# schematic.net
KiCad netlist of a schematic drawn in EasyEDA
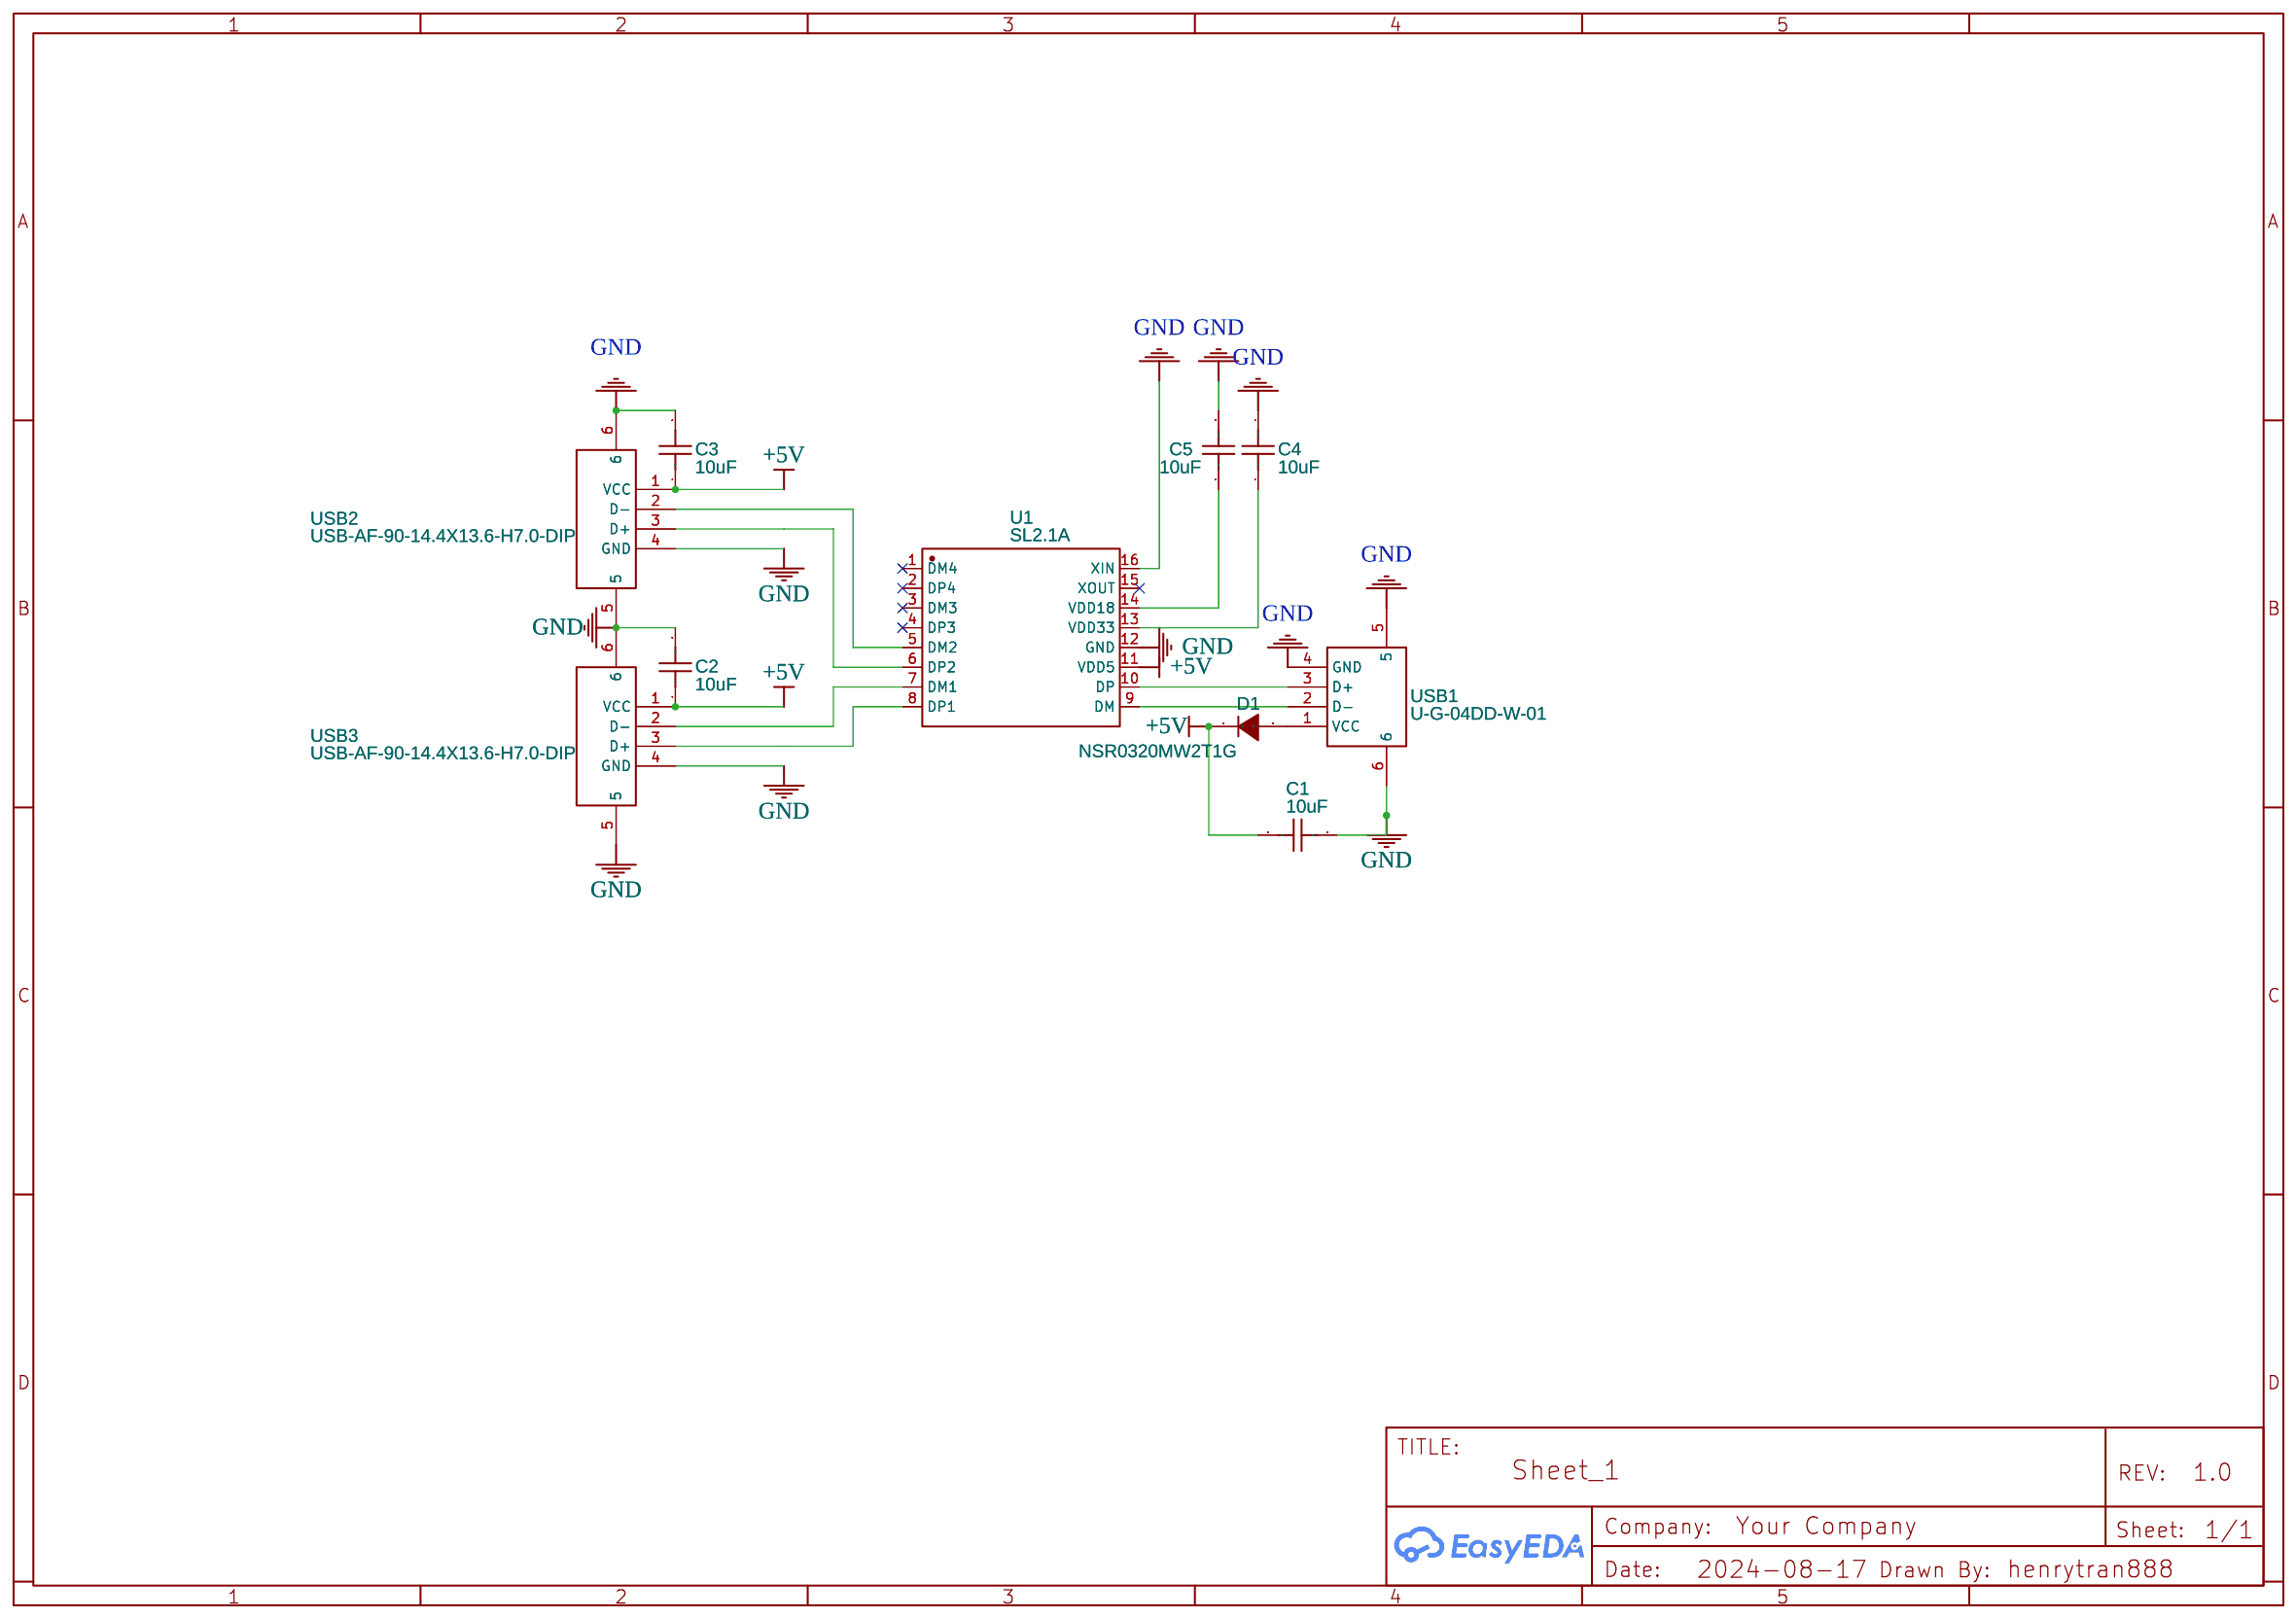
[diagram p0: schematic sheet]

(export (version "E")
  (design (tool "Eeschema 10.0.6"))
  (components
    (comp (ref "C1")
      (value "10uF")
      (fields
        (field (name "Manufacturer Part") "CL10A106KP8NNNC")
        (field (name "Manufacturer") "SAMSUNG(三星)")
      )
      (libsource (lib "") (part "CL10A106KP8NNNC_1"))
    )
    (comp (ref "C2")
      (value "10uF")
      (fields
        (field (name "Manufacturer Part") "CL10A106KP8NNNC")
        (field (name "Manufacturer") "SAMSUNG(三星)")
      )
      (libsource (lib "") (part "CL10A106KP8NNNC"))
    )
    (comp (ref "C3")
      (value "10uF")
      (fields
        (field (name "Manufacturer Part") "CL10A106KP8NNNC")
        (field (name "Manufacturer") "SAMSUNG(三星)")
      )
      (libsource (lib "") (part "CL10A106KP8NNNC"))
    )
    (comp (ref "C4")
      (value "10uF")
      (fields
        (field (name "Manufacturer Part") "CL10A106KP8NNNC")
        (field (name "Manufacturer") "SAMSUNG(三星)")
      )
      (libsource (lib "") (part "CL10A106KP8NNNC"))
    )
    (comp (ref "C5")
      (value "10uF")
      (fields
        (field (name "Manufacturer Part") "CL10A106KP8NNNC")
        (field (name "Manufacturer") "SAMSUNG(三星)")
      )
      (libsource (lib "") (part "CL10A106KP8NNNC"))
    )
    (comp (ref "D1")
      (value "NSR0320MW2T1G")
      (fields (field (name "Manufacturer") "onsemi(安森美)"))
      (libsource (lib "") (part "NSR0320MW2T1G"))
    )
    (comp (ref "U1")
      (value "SL2.1A")
      (fields (field (name "Manufacturer") "CoreChips(和芯润德)"))
      (libsource (lib "") (part "SL2.1A"))
    )
    (comp (ref "USB1")
      (value "U-G-04DD-W-01")
      (fields (field (name "Manufacturer Part") "U-G-O4DD-W-1") (field (name "Manufacturer") "韩国韩荣"))
      (libsource (lib "") (part "U-G-04DD-W-01"))
    )
    (comp (ref "USB2")
      (value "USB-AF-90-14.4X13.6-H7.0-DIP")
      (fields (field (name "Manufacturer Part") "903-131A1011D10100") (field (name "Manufacturer") "精拓金"))
      (libsource (lib "") (part "USB-AF-90-14.4X13.6-H7.0-DIP"))
    )
    (comp (ref "USB3")
      (value "USB-AF-90-14.4X13.6-H7.0-DIP")
      (fields (field (name "Manufacturer Part") "903-131A1011D10100") (field (name "Manufacturer") "精拓金"))
      (libsource (lib "") (part "USB-AF-90-14.4X13.6-H7.0-DIP"))
    )
  )
  (nets
    (net (code "1") (name "+5V") (class "Default")
      (node (ref "C1") (pin "1") (pinfunction "1_1") (pintype "unspecified"))
      (node (ref "C2") (pin "1") (pinfunction "1_1") (pintype "unspecified"))
      (node (ref "C3") (pin "1") (pinfunction "1_1") (pintype "unspecified"))
      (node (ref "D1") (pin "1") (pinfunction "C_1") (pintype "unspecified"))
      (node (ref "U1") (pin "11") (pinfunction "VDD5_11") (pintype "unspecified"))
      (node (ref "USB2") (pin "1") (pinfunction "VCC_1") (pintype "unspecified"))
      (node (ref "USB3") (pin "1") (pinfunction "VCC_1") (pintype "unspecified"))
    )
    (net (code "2") (name "GND") (class "Default")
      (node (ref "C1") (pin "2") (pinfunction "2_2") (pintype "unspecified"))
      (node (ref "C2") (pin "2") (pinfunction "2_2") (pintype "unspecified"))
      (node (ref "C3") (pin "2") (pinfunction "2_2") (pintype "unspecified"))
      (node (ref "C4") (pin "2") (pinfunction "2_2") (pintype "unspecified"))
      (node (ref "C5") (pin "2") (pinfunction "2_2") (pintype "unspecified"))
      (node (ref "U1") (pin "12") (pinfunction "GND_12") (pintype "unspecified"))
      (node (ref "U1") (pin "16") (pinfunction "XIN_16") (pintype "unspecified"))
      (node (ref "USB1") (pin "4") (pinfunction "GND_4") (pintype "unspecified"))
      (node (ref "USB1") (pin "5") (pinfunction "5_5") (pintype "unspecified"))
      (node (ref "USB1") (pin "6") (pinfunction "6_6") (pintype "unspecified"))
      (node (ref "USB2") (pin "4") (pinfunction "GND_4") (pintype "unspecified"))
      (node (ref "USB2") (pin "5") (pinfunction "5_5") (pintype "unspecified"))
      (node (ref "USB2") (pin "6") (pinfunction "6_6") (pintype "unspecified"))
      (node (ref "USB3") (pin "4") (pinfunction "GND_4") (pintype "unspecified"))
      (node (ref "USB3") (pin "5") (pinfunction "5_5") (pintype "unspecified"))
      (node (ref "USB3") (pin "6") (pinfunction "6_6") (pintype "unspecified"))
    )
    (net (code "3") (name "Net-(D1-A)") (class "Default")
      (node (ref "D1") (pin "2") (pinfunction "A_2") (pintype "unspecified"))
      (node (ref "USB1") (pin "1") (pinfunction "VCC_1") (pintype "unspecified"))
    )
    (net (code "4") (name "Net-(U1-DM)") (class "Default")
      (node (ref "U1") (pin "9") (pinfunction "DM_9") (pintype "unspecified"))
      (node (ref "USB1") (pin "2") (pinfunction "D-_2") (pintype "unspecified"))
    )
    (net (code "5") (name "Net-(U1-DM1)") (class "Default")
      (node (ref "U1") (pin "7") (pinfunction "DM1_7") (pintype "unspecified"))
      (node (ref "USB3") (pin "2") (pinfunction "D-_2") (pintype "unspecified"))
    )
    (net (code "6") (name "Net-(U1-DM2)") (class "Default")
      (node (ref "U1") (pin "5") (pinfunction "DM2_5") (pintype "unspecified"))
      (node (ref "USB2") (pin "2") (pinfunction "D-_2") (pintype "unspecified"))
    )
    (net (code "7") (name "Net-(U1-DP)") (class "Default")
      (node (ref "U1") (pin "10") (pinfunction "DP_10") (pintype "unspecified"))
      (node (ref "USB1") (pin "3") (pinfunction "D+_3") (pintype "unspecified"))
    )
    (net (code "8") (name "Net-(U1-DP1)") (class "Default")
      (node (ref "U1") (pin "8") (pinfunction "DP1_8") (pintype "unspecified"))
      (node (ref "USB3") (pin "3") (pinfunction "D+_3") (pintype "unspecified"))
    )
    (net (code "9") (name "Net-(U1-DP2)") (class "Default")
      (node (ref "U1") (pin "6") (pinfunction "DP2_6") (pintype "unspecified"))
      (node (ref "USB2") (pin "3") (pinfunction "D+_3") (pintype "unspecified"))
    )
    (net (code "10") (name "Net-(U1-VDD18)") (class "Default")
      (node (ref "C5") (pin "1") (pinfunction "1_1") (pintype "unspecified"))
      (node (ref "U1") (pin "14") (pinfunction "VDD18_14") (pintype "unspecified"))
    )
    (net (code "11") (name "Net-(U1-VDD33)") (class "Default")
      (node (ref "C4") (pin "1") (pinfunction "1_1") (pintype "unspecified"))
      (node (ref "U1") (pin "13") (pinfunction "VDD33_13") (pintype "unspecified"))
    )
    (net (code "12") (name "unconnected-(U1-DM3-Pad3)") (class "Default")
      (node (ref "U1") (pin "3") (pinfunction "DM3_3") (pintype "unspecified+no_connect"))
    )
    (net (code "13") (name "unconnected-(U1-DM4-Pad1)") (class "Default")
      (node (ref "U1") (pin "1") (pinfunction "DM4_1") (pintype "unspecified+no_connect"))
    )
    (net (code "14") (name "unconnected-(U1-DP3-Pad4)") (class "Default")
      (node (ref "U1") (pin "4") (pinfunction "DP3_4") (pintype "unspecified+no_connect"))
    )
    (net (code "15") (name "unconnected-(U1-DP4-Pad2)") (class "Default")
      (node (ref "U1") (pin "2") (pinfunction "DP4_2") (pintype "unspecified+no_connect"))
    )
    (net (code "16") (name "unconnected-(U1-XOUT-Pad15)") (class "Default")
      (node (ref "U1") (pin "15") (pinfunction "XOUT_15") (pintype "unspecified+no_connect"))
    )
  )
)
